# main.net
KiCad netlist of a schematic drawn in Altium Designer
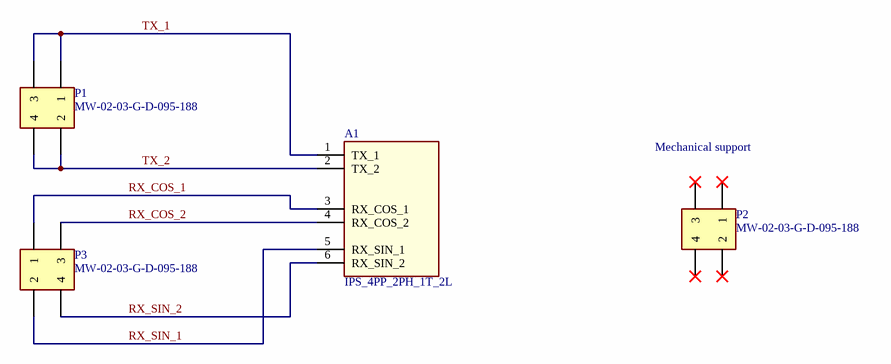
[diagram p0: main.SchDoc]

(export (version "E")
  (design (tool "Eeschema 10.0.6"))
  (components
    (comp (ref "A1")
      (value "IPS_4PP_2PH_1T_2L")
      (footprint "IPS_4PP_2PH_1T_2L_6TX035_EXT")
      (description "Inductive position sensor, 2 phase, 1 turn, 2Layers 4 Pole pairs")
      (libsource (lib "PMP_NoBomComps") (part "IPS_4PP_2PH_1T_2L"))
    )
    (comp (ref "P1")
      (value "MW-02-03-G-D-095-188")
      (footprint "SAMTEC_MW-02-03-X-D-XXX-XXX")
      (description "Samtech Male header 2x2,pitch 1mm")
      (fields (field (name "MP") "TSW-108-07-G-S") (field (name "MF") "Samtec"))
      (libsource (lib "PMP_ConnectorsDB") (part "Conn_4_STRIP_2x2"))
    )
    (comp (ref "P2")
      (value "MW-02-03-G-D-095-188")
      (footprint "SAMTEC_MW-02-03-X-D-XXX-XXX")
      (description "Samtech Male header 2x2,pitch 1mm")
      (fields (field (name "MP") "TSW-108-07-G-S") (field (name "MF") "Samtec"))
      (libsource (lib "PMP_ConnectorsDB") (part "Conn_4_STRIP_2x2"))
    )
    (comp (ref "P3")
      (value "MW-02-03-G-D-095-188")
      (footprint "SAMTEC_MW-02-03-X-D-XXX-XXX")
      (description "Samtech Male header 2x2,pitch 1mm")
      (fields (field (name "MP") "TSW-108-07-G-S") (field (name "MF") "Samtec"))
      (libsource (lib "") (part "Conn_4_STRIP_2x2_1"))
    )
  )
  (nets
    (net (code "1") (name "/RX_COS_1") (class "Default")
      (node (ref "A1") (pin "3") (pinfunction "RX_COS_1_3") (pintype "passive"))
      (node (ref "P3") (pin "01") (pinfunction "1_01") (pintype "passive"))
    )
    (net (code "2") (name "/RX_COS_2") (class "Default")
      (node (ref "A1") (pin "4") (pinfunction "RX_COS_2_4") (pintype "passive"))
      (node (ref "P3") (pin "03") (pinfunction "3_03") (pintype "passive"))
    )
    (net (code "3") (name "/RX_SIN_1") (class "Default")
      (node (ref "A1") (pin "5") (pinfunction "RX_SIN_1_5") (pintype "passive"))
      (node (ref "P3") (pin "02") (pinfunction "2_02") (pintype "passive"))
    )
    (net (code "4") (name "/RX_SIN_2") (class "Default")
      (node (ref "A1") (pin "6") (pinfunction "RX_SIN_2_6") (pintype "passive"))
      (node (ref "P3") (pin "04") (pinfunction "4_04") (pintype "passive"))
    )
    (net (code "5") (name "/TX_1") (class "Default")
      (node (ref "A1") (pin "1") (pinfunction "TX_1_1") (pintype "passive"))
      (node (ref "P1") (pin "01") (pinfunction "1_01") (pintype "passive"))
      (node (ref "P1") (pin "03") (pinfunction "3_03") (pintype "passive"))
    )
    (net (code "6") (name "/TX_2") (class "Default")
      (node (ref "A1") (pin "2") (pinfunction "TX_2_2") (pintype "passive"))
      (node (ref "P1") (pin "02") (pinfunction "2_02") (pintype "passive"))
      (node (ref "P1") (pin "04") (pinfunction "4_04") (pintype "passive"))
    )
    (net (code "7") (name "unconnected-(P2-1-Pad01)") (class "Default")
      (node (ref "P2") (pin "01") (pinfunction "1_01") (pintype "passive+no_connect"))
    )
    (net (code "8") (name "unconnected-(P2-2-Pad02)") (class "Default")
      (node (ref "P2") (pin "02") (pinfunction "2_02") (pintype "passive+no_connect"))
    )
    (net (code "9") (name "unconnected-(P2-3-Pad03)") (class "Default")
      (node (ref "P2") (pin "03") (pinfunction "3_03") (pintype "passive+no_connect"))
    )
    (net (code "10") (name "unconnected-(P2-4-Pad04)") (class "Default")
      (node (ref "P2") (pin "04") (pinfunction "4_04") (pintype "passive+no_connect"))
    )
  )
)
